# Sens_SHT2x.net
KiCad netlist of a schematic drawn in EAGLE
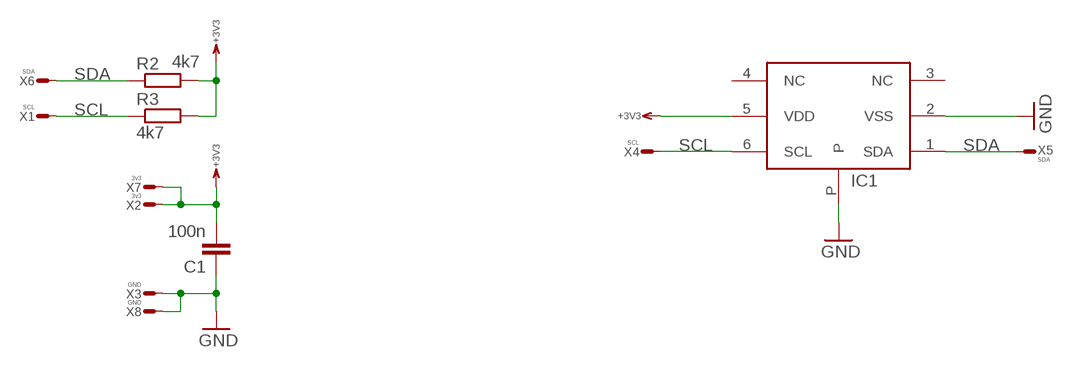
[diagram p0: schematic, sheet 1]

(export (version "E")
  (design (tool "Eeschema 10.0.6"))
  (components
    (comp (ref "C1")
      (value "100n")
      (footprint "eagle-import:0603")
      (libsource (lib "eagle-import") (part "C0603"))
    )
    (comp (ref "IC1")
      (value "SHT2X")
      (footprint "eagle-import:DFN6")
      (libsource (lib "eagle-import") (part "SHT2X"))
    )
    (comp (ref "R2")
      (value "4k7")
      (footprint "eagle-import:0603")
      (libsource (lib "eagle-import") (part "R0603"))
    )
    (comp (ref "R3")
      (value "4k7")
      (footprint "eagle-import:0603")
      (libsource (lib "eagle-import") (part "R0603"))
    )
    (comp (ref "X1")
      (value "SCL")
      (footprint "eagle-import:T1.6_0.9")
      (libsource (lib "eagle-import") (part "WIREPADT1.6/0.9"))
    )
    (comp (ref "X2")
      (value "3v3")
      (footprint "eagle-import:T1.6_0.9")
      (libsource (lib "eagle-import") (part "WIREPADT1.6/0.9"))
    )
    (comp (ref "X3")
      (value "GND")
      (footprint "eagle-import:T1.6_0.9")
      (libsource (lib "eagle-import") (part "WIREPADT1.6/0.9"))
    )
    (comp (ref "X4")
      (value "SCL")
      (footprint "eagle-import:T1.6_0.9")
      (libsource (lib "eagle-import") (part "WIREPADT1.6/0.9"))
    )
    (comp (ref "X5")
      (value "SDA")
      (footprint "eagle-import:T1.6_0.9")
      (libsource (lib "eagle-import") (part "WIREPADT1.6/0.9"))
    )
    (comp (ref "X6")
      (value "SDA")
      (footprint "eagle-import:T1.6_0.9")
      (libsource (lib "eagle-import") (part "WIREPADT1.6/0.9"))
    )
    (comp (ref "X7")
      (value "3v3")
      (footprint "eagle-import:T1.6_0.9")
      (libsource (lib "eagle-import") (part "WIREPADT1.6/0.9"))
    )
    (comp (ref "X8")
      (value "GND")
      (footprint "eagle-import:T1.6_0.9")
      (libsource (lib "eagle-import") (part "WIREPADT1.6/0.9"))
    )
  )
  (nets
    (net (code "1") (name "+3V3") (class "Default")
      (node (ref "C1") (pin "2") (pinfunction "2_2") (pintype "passive"))
      (node (ref "IC1") (pin "5") (pinfunction "VDD_5") (pintype "bidirectional"))
      (node (ref "R2") (pin "2") (pinfunction "2_2") (pintype "passive"))
      (node (ref "R3") (pin "2") (pinfunction "2_2") (pintype "passive"))
      (node (ref "X2") (pin "1") (pinfunction "S_1") (pintype "passive"))
      (node (ref "X7") (pin "1") (pinfunction "S_1") (pintype "passive"))
    )
    (net (code "2") (name "/SCL") (class "Default")
      (node (ref "IC1") (pin "6") (pinfunction "SCL_6") (pintype "bidirectional"))
      (node (ref "R3") (pin "1") (pinfunction "1_1") (pintype "passive"))
      (node (ref "X1") (pin "1") (pinfunction "S_1") (pintype "passive"))
      (node (ref "X4") (pin "1") (pinfunction "S_1") (pintype "passive"))
    )
    (net (code "3") (name "/SDA") (class "Default")
      (node (ref "IC1") (pin "1") (pinfunction "SDA_1") (pintype "bidirectional"))
      (node (ref "R2") (pin "1") (pinfunction "1_1") (pintype "passive"))
      (node (ref "X5") (pin "1") (pinfunction "S_1") (pintype "passive"))
      (node (ref "X6") (pin "1") (pinfunction "S_1") (pintype "passive"))
    )
    (net (code "4") (name "GND") (class "Default")
      (node (ref "C1") (pin "1") (pinfunction "1_1") (pintype "passive"))
      (node (ref "IC1") (pin "2") (pinfunction "VSS_2") (pintype "bidirectional"))
      (node (ref "IC1") (pin "P") (pinfunction "P_P") (pintype "bidirectional"))
      (node (ref "X3") (pin "1") (pinfunction "S_1") (pintype "passive"))
      (node (ref "X8") (pin "1") (pinfunction "S_1") (pintype "passive"))
    )
    (net (code "5") (name "unconnected-(IC1-NC-Pad3)") (class "Default")
      (node (ref "IC1") (pin "3") (pinfunction "NC_3") (pintype "bidirectional"))
    )
    (net (code "6") (name "unconnected-(IC1-NC-Pad4)") (class "Default")
      (node (ref "IC1") (pin "4") (pinfunction "NC_4") (pintype "bidirectional"))
    )
  )
)
